# HD1772.net
KiCad netlist of a schematic drawn in Altium Designer
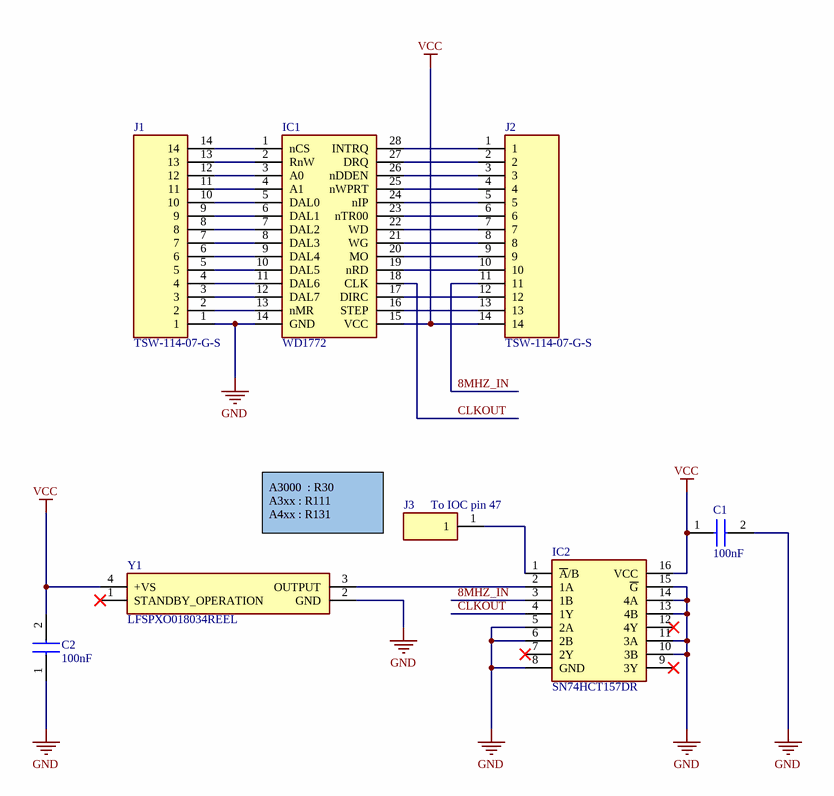
[diagram p0: HD1772.SchDoc]

(export (version "E")
  (design (tool "Eeschema 10.0.6"))
  (components
    (comp (ref "C1")
      (value "100nF")
      (footprint "SamacSys:CAPC2012X145N")
      (description "Capacitor")
      (fields
        (field (name "MANUFACTURER_PART_NUMBER") "C2012X7R1H104K125AM")
        (field (name "MOUSER PART NUMBER") "810-C2012X7R1H104KT5")
      )
      (libsource (lib "SamacSys") (part "C2012X7R1H104K125AM"))
    )
    (comp (ref "C2")
      (value "100nF")
      (footprint "SamacSys:CAPC2012X145N")
      (description "Capacitor")
      (fields
        (field (name "MANUFACTURER_PART_NUMBER") "C2012X7R1H104K125AM")
        (field (name "MOUSER PART NUMBER") "810-C2012X7R1H104KT5")
      )
      (libsource (lib "SamacSys") (part "C2012X7R1H104K125AM"))
    )
    (comp (ref "IC1")
      (value "WD1772")
      (footprint "SamacSys:DIP1556W56P254L3740H635Q28N")
      (description "Integrated Circuit")
      (libsource (lib "SamacSys") (part "WD1772"))
    )
    (comp (ref "IC2")
      (value "SN74HCT157DR")
      (footprint "SamacSys:SOIC127P600X175-16N")
      (description "Integrated Circuit")
      (fields (field (name "MOUSER PART NUMBER") "595-SN74HCT157DR"))
      (libsource (lib "*") (part "SN74HCT157DR"))
    )
    (comp (ref "J1")
      (value "TSW-114-07-G-S")
      (footprint "SamacSys:TSW-114-XX-YY-S")
      (description "Connector")
      (fields (field (name "MOUSER PART NUMBER") "200-TSW11407GS"))
      (libsource (lib "") (part "TSW-114-07-G-S_1"))
    )
    (comp (ref "J2")
      (value "TSW-114-07-G-S")
      (footprint "SamacSys:TSW-114-XX-YY-S")
      (description "Connector")
      (fields (field (name "MOUSER PART NUMBER") "200-TSW11407GS"))
      (libsource (lib "*") (part "TSW-114-07-G-S"))
    )
    (comp (ref "J3")
      (value "To IOC pin 47")
      (footprint "SamacSys:TSW-101-XX-YY-S")
      (description "Connector")
      (fields
        (field (name "MANUFACTURER_PART_NUMBER") "TSW-101-07-G-S")
        (field (name "MOUSER PART NUMBER") "200-TSW10107GS")
      )
      (libsource (lib "*") (part "TSW-101-07-G-S"))
    )
    (comp (ref "Y1")
      (value "LFSPXO018034REEL")
      (footprint "SamacSys:LFSPXO018034REEL")
      (description "Crystal or Oscillator")
      (fields (field (name "MOUSER PART NUMBER") "449-LFSPXO018034REEL"))
      (libsource (lib "*") (part "LFSPXO018034REEL"))
    )
  )
  (nets
    (net (code "1") (name "/8MHZ_IN") (class "Default")
      (node (ref "IC2") (pin "3") (pinfunction "1B_3") (pintype "passive"))
      (node (ref "J2") (pin "11") (pinfunction "11_11") (pintype "passive"))
    )
    (net (code "2") (name "/CLKOUT") (class "Default")
      (node (ref "IC1") (pin "18") (pinfunction "CLK_18") (pintype "passive"))
      (node (ref "IC2") (pin "4") (pinfunction "1Y_4") (pintype "passive"))
    )
    (net (code "3") (name "GND") (class "Default")
      (node (ref "C1") (pin "2") (pinfunction "2_2") (pintype "passive"))
      (node (ref "C2") (pin "1") (pinfunction "1_1") (pintype "passive"))
      (node (ref "IC1") (pin "14") (pinfunction "GND_14") (pintype "passive"))
      (node (ref "IC2") (pin "10") (pinfunction "3B_10") (pintype "passive"))
      (node (ref "IC2") (pin "11") (pinfunction "3A_11") (pintype "passive"))
      (node (ref "IC2") (pin "13") (pinfunction "4B_13") (pintype "passive"))
      (node (ref "IC2") (pin "14") (pinfunction "4A_14") (pintype "passive"))
      (node (ref "IC2") (pin "15") (pinfunction "~{G}_15") (pintype "passive"))
      (node (ref "IC2") (pin "5") (pinfunction "2A_5") (pintype "passive"))
      (node (ref "IC2") (pin "6") (pinfunction "2B_6") (pintype "passive"))
      (node (ref "IC2") (pin "8") (pinfunction "GND_8") (pintype "passive"))
      (node (ref "J1") (pin "1") (pinfunction "1_1") (pintype "passive"))
      (node (ref "Y1") (pin "2") (pinfunction "GND_2") (pintype "passive"))
    )
    (net (code "4") (name "Net-(IC1-A0)") (class "Default")
      (node (ref "IC1") (pin "3") (pinfunction "A0_3") (pintype "passive"))
      (node (ref "J1") (pin "12") (pinfunction "12_12") (pintype "passive"))
    )
    (net (code "5") (name "Net-(IC1-A1)") (class "Default")
      (node (ref "IC1") (pin "4") (pinfunction "A1_4") (pintype "passive"))
      (node (ref "J1") (pin "11") (pinfunction "11_11") (pintype "passive"))
    )
    (net (code "6") (name "Net-(IC1-DAL0)") (class "Default")
      (node (ref "IC1") (pin "5") (pinfunction "DAL0_5") (pintype "passive"))
      (node (ref "J1") (pin "10") (pinfunction "10_10") (pintype "passive"))
    )
    (net (code "7") (name "Net-(IC1-DAL1)") (class "Default")
      (node (ref "IC1") (pin "6") (pinfunction "DAL1_6") (pintype "passive"))
      (node (ref "J1") (pin "9") (pinfunction "9_9") (pintype "passive"))
    )
    (net (code "8") (name "Net-(IC1-DAL2)") (class "Default")
      (node (ref "IC1") (pin "7") (pinfunction "DAL2_7") (pintype "passive"))
      (node (ref "J1") (pin "8") (pinfunction "8_8") (pintype "passive"))
    )
    (net (code "9") (name "Net-(IC1-DAL3)") (class "Default")
      (node (ref "IC1") (pin "8") (pinfunction "DAL3_8") (pintype "passive"))
      (node (ref "J1") (pin "7") (pinfunction "7_7") (pintype "passive"))
    )
    (net (code "10") (name "Net-(IC1-DAL4)") (class "Default")
      (node (ref "IC1") (pin "9") (pinfunction "DAL4_9") (pintype "passive"))
      (node (ref "J1") (pin "6") (pinfunction "6_6") (pintype "passive"))
    )
    (net (code "11") (name "Net-(IC1-DAL5)") (class "Default")
      (node (ref "IC1") (pin "10") (pinfunction "DAL5_10") (pintype "passive"))
      (node (ref "J1") (pin "5") (pinfunction "5_5") (pintype "passive"))
    )
    (net (code "12") (name "Net-(IC1-DAL6)") (class "Default")
      (node (ref "IC1") (pin "11") (pinfunction "DAL6_11") (pintype "passive"))
      (node (ref "J1") (pin "4") (pinfunction "4_4") (pintype "passive"))
    )
    (net (code "13") (name "Net-(IC1-DAL7)") (class "Default")
      (node (ref "IC1") (pin "12") (pinfunction "DAL7_12") (pintype "passive"))
      (node (ref "J1") (pin "3") (pinfunction "3_3") (pintype "passive"))
    )
    (net (code "14") (name "Net-(IC1-DIRC)") (class "Default")
      (node (ref "IC1") (pin "17") (pinfunction "DIRC_17") (pintype "passive"))
      (node (ref "J2") (pin "12") (pinfunction "12_12") (pintype "passive"))
    )
    (net (code "15") (name "Net-(IC1-DRQ)") (class "Default")
      (node (ref "IC1") (pin "27") (pinfunction "DRQ_27") (pintype "passive"))
      (node (ref "J2") (pin "2") (pinfunction "2_2") (pintype "passive"))
    )
    (net (code "16") (name "Net-(IC1-INTRQ)") (class "Default")
      (node (ref "IC1") (pin "28") (pinfunction "INTRQ_28") (pintype "passive"))
      (node (ref "J2") (pin "1") (pinfunction "1_1") (pintype "passive"))
    )
    (net (code "17") (name "Net-(IC1-MO)") (class "Default")
      (node (ref "IC1") (pin "20") (pinfunction "MO_20") (pintype "passive"))
      (node (ref "J2") (pin "9") (pinfunction "9_9") (pintype "passive"))
    )
    (net (code "18") (name "Net-(IC1-RnW)") (class "Default")
      (node (ref "IC1") (pin "2") (pinfunction "RnW_2") (pintype "passive"))
      (node (ref "J1") (pin "13") (pinfunction "13_13") (pintype "passive"))
    )
    (net (code "19") (name "Net-(IC1-STEP)") (class "Default")
      (node (ref "IC1") (pin "16") (pinfunction "STEP_16") (pintype "passive"))
      (node (ref "J2") (pin "13") (pinfunction "13_13") (pintype "passive"))
    )
    (net (code "20") (name "Net-(IC1-WD)") (class "Default")
      (node (ref "IC1") (pin "22") (pinfunction "WD_22") (pintype "passive"))
      (node (ref "J2") (pin "7") (pinfunction "7_7") (pintype "passive"))
    )
    (net (code "21") (name "Net-(IC1-WG)") (class "Default")
      (node (ref "IC1") (pin "21") (pinfunction "WG_21") (pintype "passive"))
      (node (ref "J2") (pin "8") (pinfunction "8_8") (pintype "passive"))
    )
    (net (code "22") (name "Net-(IC1-nCS)") (class "Default")
      (node (ref "IC1") (pin "1") (pinfunction "nCS_1") (pintype "passive"))
      (node (ref "J1") (pin "14") (pinfunction "14_14") (pintype "passive"))
    )
    (net (code "23") (name "Net-(IC1-nDDEN)") (class "Default")
      (node (ref "IC1") (pin "26") (pinfunction "nDDEN_26") (pintype "passive"))
      (node (ref "J2") (pin "3") (pinfunction "3_3") (pintype "passive"))
    )
    (net (code "24") (name "Net-(IC1-nIP)") (class "Default")
      (node (ref "IC1") (pin "24") (pinfunction "nIP_24") (pintype "passive"))
      (node (ref "J2") (pin "5") (pinfunction "5_5") (pintype "passive"))
    )
    (net (code "25") (name "Net-(IC1-nMR)") (class "Default")
      (node (ref "IC1") (pin "13") (pinfunction "nMR_13") (pintype "passive"))
      (node (ref "J1") (pin "2") (pinfunction "2_2") (pintype "passive"))
    )
    (net (code "26") (name "Net-(IC1-nRD)") (class "Default")
      (node (ref "IC1") (pin "19") (pinfunction "nRD_19") (pintype "passive"))
      (node (ref "J2") (pin "10") (pinfunction "10_10") (pintype "passive"))
    )
    (net (code "27") (name "Net-(IC1-nTR00)") (class "Default")
      (node (ref "IC1") (pin "23") (pinfunction "nTR00_23") (pintype "passive"))
      (node (ref "J2") (pin "6") (pinfunction "6_6") (pintype "passive"))
    )
    (net (code "28") (name "Net-(IC1-nWPRT)") (class "Default")
      (node (ref "IC1") (pin "25") (pinfunction "nWPRT_25") (pintype "passive"))
      (node (ref "J2") (pin "4") (pinfunction "4_4") (pintype "passive"))
    )
    (net (code "29") (name "Net-(IC2-1A)") (class "Default")
      (node (ref "IC2") (pin "2") (pinfunction "1A_2") (pintype "passive"))
      (node (ref "Y1") (pin "3") (pinfunction "OUTPUT_3") (pintype "passive"))
    )
    (net (code "30") (name "Net-(IC2-~{A}{slash}B)") (class "Default")
      (node (ref "IC2") (pin "1") (pinfunction "~{A}/B_1") (pintype "passive"))
      (node (ref "J3") (pin "1") (pinfunction "1_1") (pintype "passive"))
    )
    (net (code "31") (name "VCC") (class "Default")
      (node (ref "C1") (pin "1") (pinfunction "1_1") (pintype "passive"))
      (node (ref "C2") (pin "2") (pinfunction "2_2") (pintype "passive"))
      (node (ref "IC1") (pin "15") (pinfunction "VCC_15") (pintype "passive"))
      (node (ref "IC2") (pin "16") (pinfunction "VCC_16") (pintype "passive"))
      (node (ref "J2") (pin "14") (pinfunction "14_14") (pintype "passive"))
      (node (ref "Y1") (pin "4") (pinfunction "+VS_4") (pintype "passive"))
    )
    (net (code "32") (name "unconnected-(IC2-2Y-Pad7)") (class "Default")
      (node (ref "IC2") (pin "7") (pinfunction "2Y_7") (pintype "passive+no_connect"))
    )
    (net (code "33") (name "unconnected-(IC2-3Y-Pad9)") (class "Default")
      (node (ref "IC2") (pin "9") (pinfunction "3Y_9") (pintype "passive+no_connect"))
    )
    (net (code "34") (name "unconnected-(IC2-4Y-Pad12)") (class "Default")
      (node (ref "IC2") (pin "12") (pinfunction "4Y_12") (pintype "passive+no_connect"))
    )
    (net (code "35") (name "unconnected-(Y1-STANDBY_OPERATION-Pad1)") (class "Default")
      (node (ref "Y1") (pin "1") (pinfunction "STANDBY_OPERATION_1") (pintype "passive+no_connect"))
    )
  )
)
